# sch_pwr.net
KiCad netlist of a schematic drawn in Altium Designer
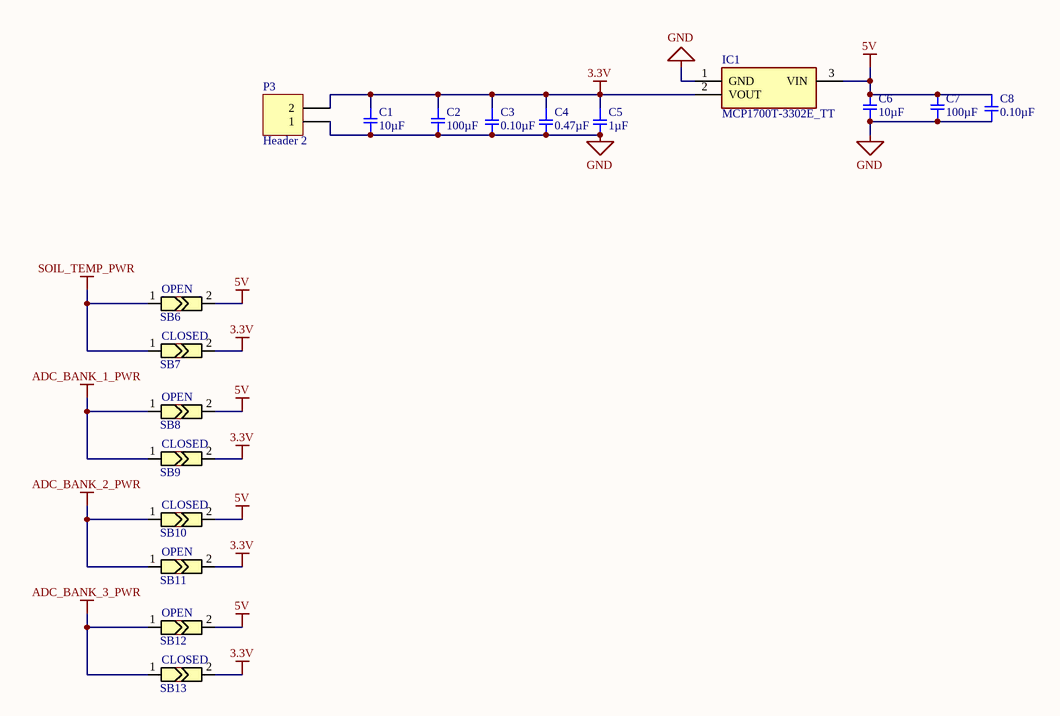
[diagram p0: sch_pwr.SchDoc]

(export (version "E")
  (design (tool "Eeschema 10.0.6"))
  (components
    (comp (ref "C1")
      (value "10µF")
      (footprint "SMD-0805C")
      (description "CAP CER 10UF 50V X7R 0805")
      (fields
        (field (name "DIGI-KEY PART NUMBER") "490-5807-1-ND")
        (field (name "PART NUMBER") "GCJ21BR71H683KA01L")
      )
      (libsource (lib "capacitor_murata_0805") (part "GCJ21BR71H683KA01L"))
    )
    (comp (ref "C2")
      (value "100µF")
      (footprint "SMD-0805C")
      (description "CAP CER 100UF 50V X7R 0805")
      (fields
        (field (name "DIGI-KEY PART NUMBER") "490-5807-1-ND")
        (field (name "PART NUMBER") "GCJ21BR71H683KA01L")
      )
      (libsource (lib "capacitor_murata_0805") (part "GCJ21BR71H683KA01L"))
    )
    (comp (ref "C3")
      (value "0.10µF")
      (footprint "SMD-0402C")
      (description "CAP CER 0.1UF 16V X7R 0402")
      (fields
        (field (name "DIGI-KEY PART NUMBER") "490-4759-1-ND")
        (field (name "PART NUMBER") "GCM155R71C104KA55D")
      )
      (libsource (lib "capacitor_murata_0402") (part "GCM155R71C104KA55D"))
    )
    (comp (ref "C4")
      (value "0.47µF")
      (footprint "SMD-0402C")
      (description "CAP CER 0.47UF 16V X7R 0402")
      (fields
        (field (name "DIGI-KEY PART NUMBER") "490-4759-1-ND")
        (field (name "PART NUMBER") "GCM155R71C104KA55D")
      )
      (libsource (lib "capacitor_murata_0402") (part "GCM155R71C104KA55D"))
    )
    (comp (ref "C5")
      (value "1µF")
      (footprint "SMD-0402C")
      (description "CAP CER 1UF 16V X7R 0402")
      (fields
        (field (name "DIGI-KEY PART NUMBER") "490-4759-1-ND")
        (field (name "PART NUMBER") "GCM155R71C104KA55D")
      )
      (libsource (lib "capacitor_murata_0402") (part "GCM155R71C104KA55D"))
    )
    (comp (ref "C6")
      (value "10µF")
      (footprint "SMD-0805C")
      (description "CAP CER 10UF 50V X7R 0805")
      (fields
        (field (name "DIGI-KEY PART NUMBER") "490-5807-1-ND")
        (field (name "PART NUMBER") "GCJ21BR71H683KA01L")
      )
      (libsource (lib "capacitor_murata_0805") (part "GCJ21BR71H683KA01L"))
    )
    (comp (ref "C7")
      (value "100µF")
      (footprint "SMD-0805C")
      (description "CAP CER 100UF 50V X7R 0805")
      (fields
        (field (name "DIGI-KEY PART NUMBER") "490-5807-1-ND")
        (field (name "PART NUMBER") "GCJ21BR71H683KA01L")
      )
      (libsource (lib "capacitor_murata_0805") (part "GCJ21BR71H683KA01L"))
    )
    (comp (ref "C8")
      (value "0.10µF")
      (footprint "SMD-0402C")
      (description "CAP CER 0.1UF 16V X7R 0402")
      (fields
        (field (name "DIGI-KEY PART NUMBER") "490-4759-1-ND")
        (field (name "PART NUMBER") "GCM155R71C104KA55D")
      )
      (libsource (lib "capacitor_murata_0402") (part "GCM155R71C104KA55D"))
    )
    (comp (ref "IC1")
      (value "MCP1700T-3302E_TT")
      (footprint "SamacSys:SOT95P237X112-3N")
      (description "Integrated Circuit")
      (fields
        (field (name "MANUFACTURER_PART_NUMBER") "MCP1700T-3302E/TT")
        (field (name "MOUSER PART NUMBER") "579-MCP1700T3302E/TT")
      )
      (libsource (lib "*") (part "MCP1700T-3302E_TT"))
    )
    (comp (ref "P3")
      (value "Header 2")
      (footprint "HDR1X2")
      (description "Header, 2-Pin")
      (fields (field (name "PUBLISHER") "Altium Limited"))
      (libsource (lib "Miscellaneous Connectors") (part "Header 2"))
    )
    (comp (ref "SB6")
      (value "SOLDER_JUMPER")
      (footprint "JUMPER_SMD")
      (libsource (lib "schematic_components") (part "SOLDER_JUMPER"))
    )
    (comp (ref "SB7")
      (value "SOLDER_JUMPER")
      (footprint "JUMPER_SMD")
      (libsource (lib "schematic_components") (part "SOLDER_JUMPER"))
    )
    (comp (ref "SB8")
      (value "SOLDER_JUMPER")
      (footprint "JUMPER_SMD")
      (libsource (lib "schematic_components") (part "SOLDER_JUMPER"))
    )
    (comp (ref "SB9")
      (value "SOLDER_JUMPER")
      (footprint "JUMPER_SMD")
      (libsource (lib "schematic_components") (part "SOLDER_JUMPER"))
    )
    (comp (ref "SB10")
      (value "SOLDER_JUMPER")
      (footprint "JUMPER_SMD")
      (libsource (lib "schematic_components") (part "SOLDER_JUMPER"))
    )
    (comp (ref "SB11")
      (value "SOLDER_JUMPER")
      (footprint "JUMPER_SMD")
      (libsource (lib "schematic_components") (part "SOLDER_JUMPER"))
    )
    (comp (ref "SB12")
      (value "SOLDER_JUMPER")
      (footprint "JUMPER_SMD")
      (libsource (lib "schematic_components") (part "SOLDER_JUMPER"))
    )
    (comp (ref "SB13")
      (value "SOLDER_JUMPER")
      (footprint "JUMPER_SMD")
      (libsource (lib "schematic_components") (part "SOLDER_JUMPER"))
    )
  )
  (nets
    (net (code "1") (name "3.3V") (class "Default")
      (node (ref "C1") (pin "2") (pinfunction "2_2") (pintype "passive"))
      (node (ref "C2") (pin "2") (pinfunction "2_2") (pintype "passive"))
      (node (ref "C3") (pin "1") (pinfunction "1_1") (pintype "passive"))
      (node (ref "C4") (pin "1") (pinfunction "1_1") (pintype "passive"))
      (node (ref "C5") (pin "1") (pinfunction "1_1") (pintype "passive"))
      (node (ref "IC1") (pin "2") (pinfunction "VOUT_2") (pintype "passive"))
      (node (ref "P3") (pin "2") (pinfunction "2_2") (pintype "passive"))
      (node (ref "SB11") (pin "2") (pinfunction "1_2") (pintype "passive"))
      (node (ref "SB13") (pin "2") (pinfunction "1_2") (pintype "passive"))
      (node (ref "SB7") (pin "2") (pinfunction "1_2") (pintype "passive"))
      (node (ref "SB9") (pin "2") (pinfunction "1_2") (pintype "passive"))
    )
    (net (code "2") (name "5V") (class "Default")
      (node (ref "C6") (pin "2") (pinfunction "2_2") (pintype "passive"))
      (node (ref "C7") (pin "2") (pinfunction "2_2") (pintype "passive"))
      (node (ref "C8") (pin "1") (pinfunction "1_1") (pintype "passive"))
      (node (ref "IC1") (pin "3") (pinfunction "VIN_3") (pintype "passive"))
      (node (ref "SB10") (pin "2") (pinfunction "1_2") (pintype "passive"))
      (node (ref "SB12") (pin "2") (pinfunction "1_2") (pintype "passive"))
      (node (ref "SB6") (pin "2") (pinfunction "1_2") (pintype "passive"))
      (node (ref "SB8") (pin "2") (pinfunction "1_2") (pintype "passive"))
    )
    (net (code "3") (name "ADC_BANK_1_PWR") (class "Default")
      (node (ref "SB8") (pin "1") (pinfunction "1_1") (pintype "passive"))
      (node (ref "SB9") (pin "1") (pinfunction "1_1") (pintype "passive"))
    )
    (net (code "4") (name "ADC_BANK_2_PWR") (class "Default")
      (node (ref "SB10") (pin "1") (pinfunction "1_1") (pintype "passive"))
      (node (ref "SB11") (pin "1") (pinfunction "1_1") (pintype "passive"))
    )
    (net (code "5") (name "ADC_BANK_3_PWR") (class "Default")
      (node (ref "SB12") (pin "1") (pinfunction "1_1") (pintype "passive"))
      (node (ref "SB13") (pin "1") (pinfunction "1_1") (pintype "passive"))
    )
    (net (code "6") (name "GND") (class "Default")
      (node (ref "C1") (pin "1") (pinfunction "1_1") (pintype "passive"))
      (node (ref "C2") (pin "1") (pinfunction "1_1") (pintype "passive"))
      (node (ref "C3") (pin "2") (pinfunction "2_2") (pintype "passive"))
      (node (ref "C4") (pin "2") (pinfunction "2_2") (pintype "passive"))
      (node (ref "C5") (pin "2") (pinfunction "2_2") (pintype "passive"))
      (node (ref "C6") (pin "1") (pinfunction "1_1") (pintype "passive"))
      (node (ref "C7") (pin "1") (pinfunction "1_1") (pintype "passive"))
      (node (ref "C8") (pin "2") (pinfunction "2_2") (pintype "passive"))
      (node (ref "IC1") (pin "1") (pinfunction "GND_1") (pintype "passive"))
      (node (ref "P3") (pin "1") (pinfunction "1_1") (pintype "passive"))
    )
    (net (code "7") (name "SOIL_TEMP_PWR") (class "Default")
      (node (ref "SB6") (pin "1") (pinfunction "1_1") (pintype "passive"))
      (node (ref "SB7") (pin "1") (pinfunction "1_1") (pintype "passive"))
    )
  )
)
